# ECB02-Kit-V1_0.net
KiCad netlist of a schematic drawn in Altium Designer
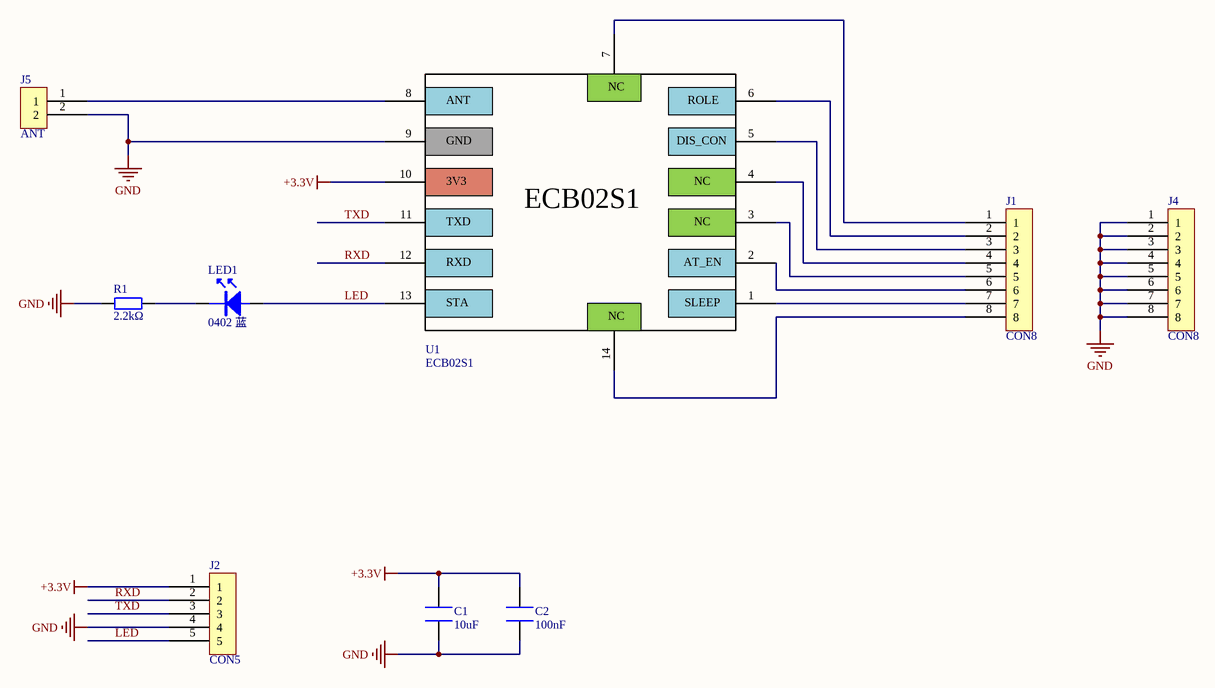
[diagram p0: ECB02-Kit-V1.0.SchDoc]

(export (version "E")
  (design (tool "Eeschema 10.0.6"))
  (components
    (comp (ref "C1") (value "10uF") (footprint "0402") (libsource (lib "ECB01-Kit-V1.0") (part "C")))
    (comp (ref "C2") (value "100nF") (footprint "0402") (libsource (lib "ECB01-Kit-V1.0") (part "C")))
    (comp (ref "J1") (value "CON8") (footprint "SIP08") (libsource (lib "ECB02-Kit-V1.0") (part "CON8")))
    (comp (ref "J2") (value "CON5") (footprint "SIP05") (libsource (lib "ECB02-Kit-V1.0") (part "CON5")))
    (comp (ref "J4") (value "CON8") (footprint "SIP08") (libsource (lib "ECB02-Kit-V1.0") (part "CON8")))
    (comp (ref "J5") (value "ANT") (footprint "ANT-2.4G-1") (libsource (lib "ECB02-Kit-V1.0") (part "ANT")))
    (comp (ref "LED1")
      (value "0402 蓝")
      (footprint "0402-led")
      (libsource (lib "ECB01-Kit-V1.0") (part "LED-0402"))
    )
    (comp (ref "R1") (value "2.2kΩ") (footprint "0402") (libsource (lib "ECB01-Kit-V1.0") (part "R")))
    (comp (ref "U1") (value "ECB02S1") (libsource (lib "ECB02蓝牙模块原理图库") (part "ECB02S1")))
  )
  (nets
    (net (code "1") (name "+3.3V") (class "Default")
      (node (ref "C1") (pin "2") (pinfunction "2_2") (pintype "passive"))
      (node (ref "C2") (pin "2") (pinfunction "2_2") (pintype "passive"))
      (node (ref "J2") (pin "1") (pinfunction "1_1") (pintype "passive"))
      (node (ref "U1") (pin "10") (pinfunction "10_10") (pintype "passive"))
    )
    (net (code "2") (name "/LED") (class "Default")
      (node (ref "J2") (pin "5") (pinfunction "5_5") (pintype "passive"))
      (node (ref "LED1") (pin "1") (pinfunction "1_1") (pintype "passive"))
      (node (ref "U1") (pin "13") (pinfunction "STA_13") (pintype "passive"))
    )
    (net (code "3") (name "/RXD") (class "Default")
      (node (ref "J2") (pin "2") (pinfunction "2_2") (pintype "passive"))
      (node (ref "U1") (pin "12") (pinfunction "12_12") (pintype "passive"))
    )
    (net (code "4") (name "/TXD") (class "Default")
      (node (ref "J2") (pin "3") (pinfunction "3_3") (pintype "passive"))
      (node (ref "U1") (pin "11") (pinfunction "11_11") (pintype "passive"))
    )
    (net (code "5") (name "GND") (class "Default")
      (node (ref "C1") (pin "1") (pinfunction "1_1") (pintype "passive"))
      (node (ref "C2") (pin "1") (pinfunction "1_1") (pintype "passive"))
      (node (ref "J2") (pin "4") (pinfunction "4_4") (pintype "passive"))
      (node (ref "J4") (pin "1") (pinfunction "1_1") (pintype "passive"))
      (node (ref "J4") (pin "2") (pinfunction "2_2") (pintype "passive"))
      (node (ref "J4") (pin "3") (pinfunction "3_3") (pintype "passive"))
      (node (ref "J4") (pin "4") (pinfunction "4_4") (pintype "passive"))
      (node (ref "J4") (pin "5") (pinfunction "5_5") (pintype "passive"))
      (node (ref "J4") (pin "6") (pinfunction "6_6") (pintype "passive"))
      (node (ref "J4") (pin "7") (pinfunction "7_7") (pintype "passive"))
      (node (ref "J4") (pin "8") (pinfunction "8_8") (pintype "passive"))
      (node (ref "J5") (pin "2") (pinfunction "2_2") (pintype "passive"))
      (node (ref "R1") (pin "2") (pinfunction "2_2") (pintype "passive"))
      (node (ref "U1") (pin "9") (pinfunction "9_9") (pintype "passive"))
    )
    (net (code "6") (name "Net-(J1-Pad1)") (class "Default")
      (node (ref "J1") (pin "1") (pinfunction "1_1") (pintype "passive"))
      (node (ref "U1") (pin "7") (pinfunction "7_7") (pintype "passive"))
    )
    (net (code "7") (name "Net-(J1-Pad2)") (class "Default")
      (node (ref "J1") (pin "2") (pinfunction "2_2") (pintype "passive"))
      (node (ref "U1") (pin "6") (pinfunction "6_6") (pintype "passive"))
    )
    (net (code "8") (name "Net-(J1-Pad3)") (class "Default")
      (node (ref "J1") (pin "3") (pinfunction "3_3") (pintype "passive"))
      (node (ref "U1") (pin "5") (pinfunction "5_5") (pintype "passive"))
    )
    (net (code "9") (name "Net-(J1-Pad4)") (class "Default")
      (node (ref "J1") (pin "4") (pinfunction "4_4") (pintype "passive"))
      (node (ref "U1") (pin "4") (pinfunction "4_4") (pintype "passive"))
    )
    (net (code "10") (name "Net-(J1-Pad5)") (class "Default")
      (node (ref "J1") (pin "5") (pinfunction "5_5") (pintype "passive"))
      (node (ref "U1") (pin "3") (pinfunction "3_3") (pintype "passive"))
    )
    (net (code "11") (name "Net-(J1-Pad6)") (class "Default")
      (node (ref "J1") (pin "6") (pinfunction "6_6") (pintype "passive"))
      (node (ref "U1") (pin "2") (pinfunction "2_2") (pintype "passive"))
    )
    (net (code "12") (name "Net-(J1-Pad7)") (class "Default")
      (node (ref "J1") (pin "7") (pinfunction "7_7") (pintype "passive"))
      (node (ref "U1") (pin "1") (pinfunction "1_1") (pintype "passive"))
    )
    (net (code "13") (name "Net-(J1-Pad8)") (class "Default")
      (node (ref "J1") (pin "8") (pinfunction "8_8") (pintype "passive"))
      (node (ref "U1") (pin "14") (pinfunction "14_14") (pintype "passive"))
    )
    (net (code "14") (name "Net-(J5-Pad1)") (class "Default")
      (node (ref "J5") (pin "1") (pinfunction "1_1") (pintype "passive"))
      (node (ref "U1") (pin "8") (pinfunction "8_8") (pintype "passive"))
    )
    (net (code "15") (name "Net-(LED1-Pad2)") (class "Default")
      (node (ref "LED1") (pin "2") (pinfunction "2_2") (pintype "passive"))
      (node (ref "R1") (pin "1") (pinfunction "1_1") (pintype "passive"))
    )
  )
)
